# ds18b20-stm32f103.net
KiCad netlist of a schematic drawn in EAGLE
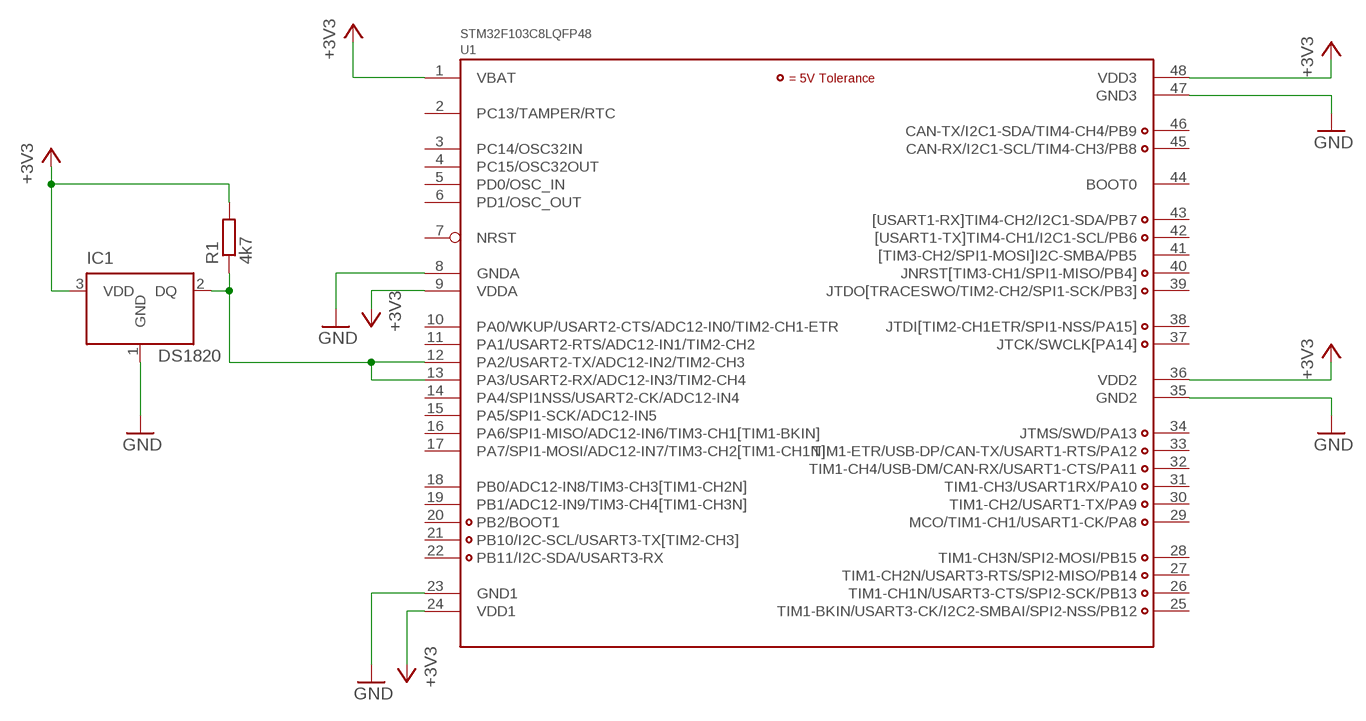
[diagram p0: schematic, sheet 1]

(export (version "E")
  (design (tool "Eeschema 10.0.6"))
  (components
    (comp (ref "IC1")
      (value "DS1820")
      (footprint "eagle-import:TO-92")
      (libsource (lib "eagle-import") (part "DS1820"))
    )
    (comp (ref "R1")
      (value "4k7")
      (footprint "eagle-import:R0805")
      (libsource (lib "eagle-import") (part "R-EU_R0805"))
    )
    (comp (ref "U1")
      (value "STM32F103C8LQFP48")
      (footprint "eagle-import:LQFP48")
      (libsource (lib "eagle-import") (part "STM32F103C8LQFP48"))
    )
  )
  (nets
    (net (code "1") (name "+3V3") (class "Default")
      (node (ref "IC1") (pin "3") (pinfunction "VDD_3") (pintype "input"))
      (node (ref "R1") (pin "2") (pinfunction "2_2") (pintype "passive"))
      (node (ref "U1") (pin "1") (pinfunction "VBAT_1") (pintype "power_in"))
      (node (ref "U1") (pin "24") (pinfunction "VDD1_24") (pintype "power_in"))
      (node (ref "U1") (pin "36") (pinfunction "VDD2_36") (pintype "power_in"))
      (node (ref "U1") (pin "48") (pinfunction "VDD3_48") (pintype "power_in"))
      (node (ref "U1") (pin "9") (pinfunction "VDDA_9") (pintype "power_in"))
    )
    (net (code "2") (name "GND") (class "Default")
      (node (ref "IC1") (pin "1") (pinfunction "GND_1") (pintype "power_in"))
      (node (ref "U1") (pin "23") (pinfunction "GND1_23") (pintype "power_in"))
      (node (ref "U1") (pin "35") (pinfunction "GND2_35") (pintype "power_in"))
      (node (ref "U1") (pin "47") (pinfunction "GND3_47") (pintype "power_in"))
      (node (ref "U1") (pin "8") (pinfunction "GNDA_8") (pintype "power_in"))
    )
    (net (code "3") (name "Net-(IC1-DQ)") (class "Default")
      (node (ref "IC1") (pin "2") (pinfunction "DQ_2") (pintype "output"))
      (node (ref "R1") (pin "1") (pinfunction "1_1") (pintype "passive"))
      (node (ref "U1") (pin "12") (pinfunction "PA2/USART2-TX/ADC12-IN2/TIM2-CH3_12") (pintype "bidirectional"))
      (node (ref "U1") (pin "13") (pinfunction "PA3/USART2-RX/ADC12-IN3/TIM2-CH4_13") (pintype "bidirectional"))
    )
    (net (code "4") (name "unconnected-(U1-BOOT0-Pad44)") (class "Default")
      (node (ref "U1") (pin "44") (pinfunction "BOOT0_44") (pintype "bidirectional"))
    )
    (net (code "5") (name "unconnected-(U1-CAN-RX{slash}I2C1-SCL{slash}TIM4-CH3{slash}PB8-Pad45)") (class "Default")
      (node (ref "U1") (pin "45") (pinfunction "CAN-RX/I2C1-SCL/TIM4-CH3/PB8_45") (pintype "bidirectional"))
    )
    (net (code "6") (name "unconnected-(U1-CAN-TX{slash}I2C1-SDA{slash}TIM4-CH4{slash}PB9-Pad46)") (class "Default")
      (node (ref "U1") (pin "46") (pinfunction "CAN-TX/I2C1-SDA/TIM4-CH4/PB9_46") (pintype "bidirectional"))
    )
    (net (code "7") (name "unconnected-(U1-JNRST[TIM3-CH1{slash}SPI1-MISO{slash}PB4]-Pad40)") (class "Default")
      (node (ref "U1") (pin "40") (pinfunction "JNRST[TIM3-CH1/SPI1-MISO/PB4]_40") (pintype "bidirectional"))
    )
    (net (code "8") (name "unconnected-(U1-JTCK{slash}SWCLK[PA14]-Pad37)") (class "Default")
      (node (ref "U1") (pin "37") (pinfunction "JTCK/SWCLK[PA14]_37") (pintype "bidirectional"))
    )
    (net (code "9") (name "unconnected-(U1-JTDI[TIM2-CH1ETR{slash}SPI1-NSS{slash}PA15]-Pad38)") (class "Default")
      (node (ref "U1") (pin "38") (pinfunction "JTDI[TIM2-CH1ETR/SPI1-NSS/PA15]_38") (pintype "bidirectional"))
    )
    (net (code "10") (name "unconnected-(U1-JTDO[TRACESWO{slash}TIM2-CH2{slash}SPI1-SCK{slash}PB3]-Pad39)") (class "Default")
      (node (ref "U1") (pin "39") (pinfunction "JTDO[TRACESWO/TIM2-CH2/SPI1-SCK/PB3]_39") (pintype "bidirectional"))
    )
    (net (code "11") (name "unconnected-(U1-JTMS{slash}SWD{slash}PA13-Pad34)") (class "Default")
      (node (ref "U1") (pin "34") (pinfunction "JTMS/SWD/PA13_34") (pintype "bidirectional"))
    )
    (net (code "12") (name "unconnected-(U1-MCO{slash}TIM1-CH1{slash}USART1-CK{slash}PA8-Pad29)") (class "Default")
      (node (ref "U1") (pin "29") (pinfunction "MCO/TIM1-CH1/USART1-CK/PA8_29") (pintype "bidirectional"))
    )
    (net (code "13") (name "unconnected-(U1-NRST-Pad7)") (class "Default")
      (node (ref "U1") (pin "7") (pinfunction "NRST_7") (pintype "bidirectional"))
    )
    (net (code "14") (name "unconnected-(U1-PA0{slash}WKUP{slash}USART2-CTS{slash}ADC12-IN0{slash}TIM2-CH1-ETR-Pad10)") (class "Default")
      (node (ref "U1") (pin "10") (pinfunction "PA0/WKUP/USART2-CTS/ADC12-IN0/TIM2-CH1-ETR_10") (pintype "bidirectional"))
    )
    (net (code "15") (name "unconnected-(U1-PA1{slash}USART2-RTS{slash}ADC12-IN1{slash}TIM2-CH2-Pad11)") (class "Default")
      (node (ref "U1") (pin "11") (pinfunction "PA1/USART2-RTS/ADC12-IN1/TIM2-CH2_11") (pintype "bidirectional"))
    )
    (net (code "16") (name "unconnected-(U1-PA4{slash}SPI1NSS{slash}USART2-CK{slash}ADC12-IN4-Pad14)") (class "Default")
      (node (ref "U1") (pin "14") (pinfunction "PA4/SPI1NSS/USART2-CK/ADC12-IN4_14") (pintype "bidirectional"))
    )
    (net (code "17") (name "unconnected-(U1-PA5{slash}SPI1-SCK{slash}ADC12-IN5-Pad15)") (class "Default")
      (node (ref "U1") (pin "15") (pinfunction "PA5/SPI1-SCK/ADC12-IN5_15") (pintype "bidirectional"))
    )
    (net (code "18") (name "unconnected-(U1-PA6{slash}SPI1-MISO{slash}ADC12-IN6{slash}TIM3-CH1[TIM1-BKIN]-Pad16)") (class "Default")
      (node (ref "U1") (pin "16") (pinfunction "PA6/SPI1-MISO/ADC12-IN6/TIM3-CH1[TIM1-BKIN]_16") (pintype "bidirectional"))
    )
    (net (code "19") (name "unconnected-(U1-PA7{slash}SPI1-MOSI{slash}ADC12-IN7{slash}TIM3-CH2[TIM1-CH1N]-Pad17)") (class "Default")
      (node (ref "U1") (pin "17") (pinfunction "PA7/SPI1-MOSI/ADC12-IN7/TIM3-CH2[TIM1-CH1N]_17") (pintype "bidirectional"))
    )
    (net (code "20") (name "unconnected-(U1-PB0{slash}ADC12-IN8{slash}TIM3-CH3[TIM1-CH2N]-Pad18)") (class "Default")
      (node (ref "U1") (pin "18") (pinfunction "PB0/ADC12-IN8/TIM3-CH3[TIM1-CH2N]_18") (pintype "bidirectional"))
    )
    (net (code "21") (name "unconnected-(U1-PB1{slash}ADC12-IN9{slash}TIM3-CH4[TIM1-CH3N]-Pad19)") (class "Default")
      (node (ref "U1") (pin "19") (pinfunction "PB1/ADC12-IN9/TIM3-CH4[TIM1-CH3N]_19") (pintype "bidirectional"))
    )
    (net (code "22") (name "unconnected-(U1-PB2{slash}BOOT1-Pad20)") (class "Default")
      (node (ref "U1") (pin "20") (pinfunction "PB2/BOOT1_20") (pintype "bidirectional"))
    )
    (net (code "23") (name "unconnected-(U1-PB10{slash}I2C-SCL{slash}USART3-TX[TIM2-CH3]-Pad21)") (class "Default")
      (node (ref "U1") (pin "21") (pinfunction "PB10/I2C-SCL/USART3-TX[TIM2-CH3]_21") (pintype "bidirectional"))
    )
    (net (code "24") (name "unconnected-(U1-PB11{slash}I2C-SDA{slash}USART3-RX-Pad22)") (class "Default")
      (node (ref "U1") (pin "22") (pinfunction "PB11/I2C-SDA/USART3-RX_22") (pintype "bidirectional"))
    )
    (net (code "25") (name "unconnected-(U1-PC13{slash}TAMPER{slash}RTC-Pad2)") (class "Default")
      (node (ref "U1") (pin "2") (pinfunction "PC13/TAMPER/RTC_2") (pintype "bidirectional"))
    )
    (net (code "26") (name "unconnected-(U1-PC14{slash}OSC32IN-Pad3)") (class "Default")
      (node (ref "U1") (pin "3") (pinfunction "PC14/OSC32IN_3") (pintype "bidirectional"))
    )
    (net (code "27") (name "unconnected-(U1-PC15{slash}OSC32OUT-Pad4)") (class "Default")
      (node (ref "U1") (pin "4") (pinfunction "PC15/OSC32OUT_4") (pintype "bidirectional"))
    )
    (net (code "28") (name "unconnected-(U1-PD0{slash}OSC_IN-Pad5)") (class "Default")
      (node (ref "U1") (pin "5") (pinfunction "PD0/OSC_IN_5") (pintype "bidirectional"))
    )
    (net (code "29") (name "unconnected-(U1-PD1{slash}OSC_OUT-Pad6)") (class "Default")
      (node (ref "U1") (pin "6") (pinfunction "PD1/OSC_OUT_6") (pintype "bidirectional"))
    )
    (net (code "30") (name "unconnected-(U1-TIM1-BKIN{slash}USART3-CK{slash}I2C2-SMBAI{slash}SPI2-NSS{slash}PB12-Pad25)") (class "Default")
      (node (ref "U1") (pin "25") (pinfunction "TIM1-BKIN/USART3-CK/I2C2-SMBAI/SPI2-NSS/PB12_25") (pintype "bidirectional"))
    )
    (net (code "31") (name "unconnected-(U1-TIM1-CH1N{slash}USART3-CTS{slash}SPI2-SCK{slash}PB13-Pad26)") (class "Default")
      (node (ref "U1") (pin "26") (pinfunction "TIM1-CH1N/USART3-CTS/SPI2-SCK/PB13_26") (pintype "bidirectional"))
    )
    (net (code "32") (name "unconnected-(U1-TIM1-CH2N{slash}USART3-RTS{slash}SPI2-MISO{slash}PB14-Pad27)") (class "Default")
      (node (ref "U1") (pin "27") (pinfunction "TIM1-CH2N/USART3-RTS/SPI2-MISO/PB14_27") (pintype "bidirectional"))
    )
    (net (code "33") (name "unconnected-(U1-TIM1-CH2{slash}USART1-TX{slash}PA9-Pad30)") (class "Default")
      (node (ref "U1") (pin "30") (pinfunction "TIM1-CH2/USART1-TX/PA9_30") (pintype "bidirectional"))
    )
    (net (code "34") (name "unconnected-(U1-TIM1-CH3N{slash}SPI2-MOSI{slash}PB15-Pad28)") (class "Default")
      (node (ref "U1") (pin "28") (pinfunction "TIM1-CH3N/SPI2-MOSI/PB15_28") (pintype "bidirectional"))
    )
    (net (code "35") (name "unconnected-(U1-TIM1-CH3{slash}USART1RX{slash}PA10-Pad31)") (class "Default")
      (node (ref "U1") (pin "31") (pinfunction "TIM1-CH3/USART1RX/PA10_31") (pintype "bidirectional"))
    )
    (net (code "36") (name "unconnected-(U1-TIM1-CH4{slash}USB-DM{slash}CAN-RX{slash}USART1-CTS{slash}PA11-Pad32)") (class "Default")
      (node (ref "U1") (pin "32") (pinfunction "TIM1-CH4/USB-DM/CAN-RX/USART1-CTS/PA11_32") (pintype "bidirectional"))
    )
    (net (code "37") (name "unconnected-(U1-TIM1-ETR{slash}USB-DP{slash}CAN-TX{slash}USART1-RTS{slash}PA12-Pad33)") (class "Default")
      (node (ref "U1") (pin "33") (pinfunction "TIM1-ETR/USB-DP/CAN-TX/USART1-RTS/PA12_33") (pintype "bidirectional"))
    )
    (net (code "38") (name "unconnected-(U1-[TIM3-CH2{slash}SPI1-MOSI]I2C-SMBA{slash}PB5-Pad41)") (class "Default")
      (node (ref "U1") (pin "41") (pinfunction "[TIM3-CH2/SPI1-MOSI]I2C-SMBA/PB5_41") (pintype "bidirectional"))
    )
    (net (code "39") (name "unconnected-(U1-[USART1-RX]TIM4-CH2{slash}I2C1-SDA{slash}PB7-Pad43)") (class "Default")
      (node (ref "U1") (pin "43") (pinfunction "[USART1-RX]TIM4-CH2/I2C1-SDA/PB7_43") (pintype "bidirectional"))
    )
    (net (code "40") (name "unconnected-(U1-[USART1-TX]TIM4-CH1{slash}I2C1-SCL{slash}PB6-Pad42)") (class "Default")
      (node (ref "U1") (pin "42") (pinfunction "[USART1-TX]TIM4-CH1/I2C1-SCL/PB6_42") (pintype "bidirectional"))
    )
  )
)
